# leslius.net
KiCad netlist of a schematic drawn in EAGLE
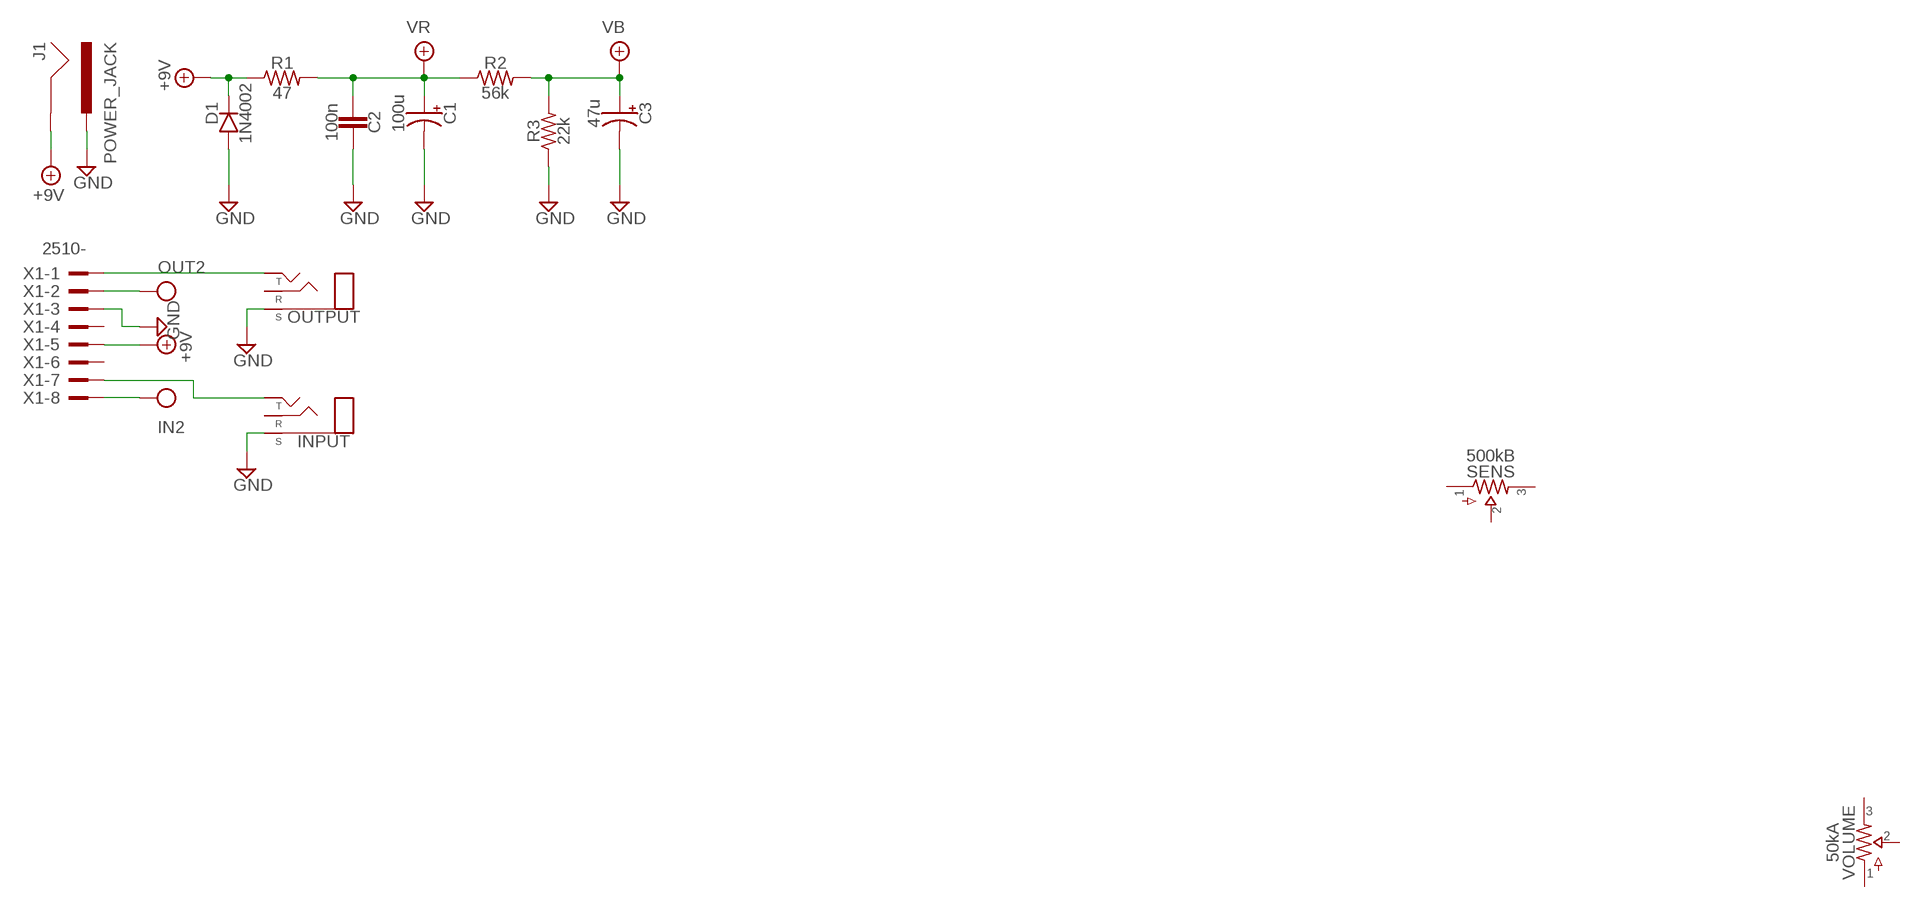
[diagram p0: schematic, sheet 1]

(export (version "E")
  (design (tool "Eeschema 10.0.6"))
  (components
    (comp (ref "C1")
      (value "100u")
      (footprint "eagle-import:040_020")
      (libsource (lib "eagle-import") (part "0400"))
    )
    (comp (ref "C2")
      (value "100n")
      (footprint "eagle-import:050X030_025_2")
      (libsource (lib "eagle-import") (part "CER/FILM2"))
    )
    (comp (ref "C3")
      (value "47u")
      (footprint "eagle-import:040_020")
      (libsource (lib "eagle-import") (part "0400"))
    )
    (comp (ref "D1")
      (value "1N4002")
      (footprint "eagle-import:DO41-2")
      (libsource (lib "eagle-import") (part "DO41.2"))
    )
    (comp (ref "INPUT")
      (value "STEREONMJ")
      (footprint "eagle-import:NMJ6HCD2")
      (libsource (lib "eagle-import") (part "STEREONMJ"))
    )
    (comp (ref "J1")
      (value "POWER_JACK")
      (footprint "eagle-import:POWER_JACK_PTH")
      (libsource (lib "eagle-import") (part "POWER_JACK"))
    )
    (comp (ref "OUTPUT")
      (value "STEREONMJ")
      (footprint "eagle-import:NMJ6HCD2")
      (libsource (lib "eagle-import") (part "STEREONMJ"))
    )
    (comp (ref "R1")
      (value "47")
      (footprint "eagle-import:R0207_3")
      (libsource (lib "eagle-import") (part "R_.3B"))
    )
    (comp (ref "R2")
      (value "56k")
      (footprint "eagle-import:R0207_3")
      (libsource (lib "eagle-import") (part "R_.3B"))
    )
    (comp (ref "R3")
      (value "22k")
      (footprint "eagle-import:R0207_3")
      (libsource (lib "eagle-import") (part "R_.3B"))
    )
    (comp (ref "SENS")
      (value "500kB")
      (footprint "eagle-import:16MM")
      (libsource (lib "eagle-import") (part "POTS16MM"))
    )
    (comp (ref "VOLUME")
      (value "50kA")
      (footprint "eagle-import:16MM")
      (libsource (lib "eagle-import") (part "POTS16MM"))
    )
    (comp (ref "X1")
      (value "2510-")
      (footprint "eagle-import:PAK100_2500-10")
      (fields (field (name "MF") "3M") (field (name "MPN") "2510-6002UB"))
      (libsource (lib "eagle-import") (part "2510-"))
    )
  )
  (nets
    (net (code "1") (name "+9V") (class "Default")
      (node (ref "D1") (pin "C") (pinfunction "C_C") (pintype "passive"))
      (node (ref "J1") (pin "GND") (pinfunction "GND_GND") (pintype "bidirectional"))
      (node (ref "R1") (pin "1") (pinfunction "1_1") (pintype "passive"))
      (node (ref "X1") (pin "5") (pinfunction "KL_5") (pintype "passive"))
    )
    (net (code "2") (name "GND") (class "Default")
      (node (ref "C1") (pin "-") (pinfunction "-_-") (pintype "passive"))
      (node (ref "C2") (pin "1") (pinfunction "1_1") (pintype "passive"))
      (node (ref "C3") (pin "-") (pinfunction "-_-") (pintype "passive"))
      (node (ref "D1") (pin "A") (pinfunction "A_A") (pintype "passive"))
      (node (ref "INPUT") (pin "S") (pinfunction "S_S") (pintype "passive"))
      (node (ref "J1") (pin "PWR") (pinfunction "PWR_PWR") (pintype "bidirectional"))
      (node (ref "OUTPUT") (pin "S") (pinfunction "S_S") (pintype "passive"))
      (node (ref "R3") (pin "1") (pinfunction "1_1") (pintype "passive"))
      (node (ref "X1") (pin "3") (pinfunction "KL_3") (pintype "passive"))
    )
    (net (code "3") (name "IN") (class "Default")
      (node (ref "X1") (pin "8") (pinfunction "KL_8") (pintype "passive"))
    )
    (net (code "4") (name "Net-(X1A-KL)") (class "Default")
      (node (ref "OUTPUT") (pin "T") (pinfunction "T_T") (pintype "passive"))
      (node (ref "X1") (pin "1") (pinfunction "KL_1") (pintype "passive"))
    )
    (net (code "5") (name "Net-(X1G-KL)") (class "Default")
      (node (ref "INPUT") (pin "T") (pinfunction "T_T") (pintype "passive"))
      (node (ref "X1") (pin "7") (pinfunction "KL_7") (pintype "passive"))
    )
    (net (code "6") (name "OUT") (class "Default")
      (node (ref "X1") (pin "2") (pinfunction "KL_2") (pintype "passive"))
    )
    (net (code "7") (name "VB") (class "Default")
      (node (ref "C3") (pin "+") (pinfunction "+_+") (pintype "passive"))
      (node (ref "R2") (pin "2") (pinfunction "2_2") (pintype "passive"))
      (node (ref "R3") (pin "2") (pinfunction "2_2") (pintype "passive"))
    )
    (net (code "8") (name "VR") (class "Default")
      (node (ref "C1") (pin "+") (pinfunction "+_+") (pintype "passive"))
      (node (ref "C2") (pin "2") (pinfunction "2_2") (pintype "passive"))
      (node (ref "R1") (pin "2") (pinfunction "2_2") (pintype "passive"))
      (node (ref "R2") (pin "1") (pinfunction "1_1") (pintype "passive"))
    )
    (net (code "9") (name "unconnected-(INPUT-PadR)") (class "Default")
      (node (ref "INPUT") (pin "R") (pinfunction "R_R") (pintype "passive"))
    )
    (net (code "10") (name "unconnected-(OUTPUT-PadR)") (class "Default")
      (node (ref "OUTPUT") (pin "R") (pinfunction "R_R") (pintype "passive"))
    )
    (net (code "11") (name "unconnected-(SENS-Pad1)") (class "Default")
      (node (ref "SENS") (pin "1") (pinfunction "1_1") (pintype "passive"))
    )
    (net (code "12") (name "unconnected-(SENS-Pad2)") (class "Default")
      (node (ref "SENS") (pin "2") (pinfunction "2_2") (pintype "passive"))
    )
    (net (code "13") (name "unconnected-(SENS-Pad3)") (class "Default")
      (node (ref "SENS") (pin "3") (pinfunction "3_3") (pintype "passive"))
    )
    (net (code "14") (name "unconnected-(VOLUME-Pad1)") (class "Default")
      (node (ref "VOLUME") (pin "1") (pinfunction "1_1") (pintype "passive"))
    )
    (net (code "15") (name "unconnected-(VOLUME-Pad2)") (class "Default")
      (node (ref "VOLUME") (pin "2") (pinfunction "2_2") (pintype "passive"))
    )
    (net (code "16") (name "unconnected-(VOLUME-Pad3)") (class "Default")
      (node (ref "VOLUME") (pin "3") (pinfunction "3_3") (pintype "passive"))
    )
    (net (code "17") (name "unconnected-(X1D-KL-Pad4)") (class "Default")
      (node (ref "X1") (pin "4") (pinfunction "KL_4") (pintype "passive"))
    )
    (net (code "18") (name "unconnected-(X1F-KL-Pad6)") (class "Default")
      (node (ref "X1") (pin "6") (pinfunction "KL_6") (pintype "passive"))
    )
  )
)
